# regulator.net
KiCad netlist of a schematic drawn in EAGLE
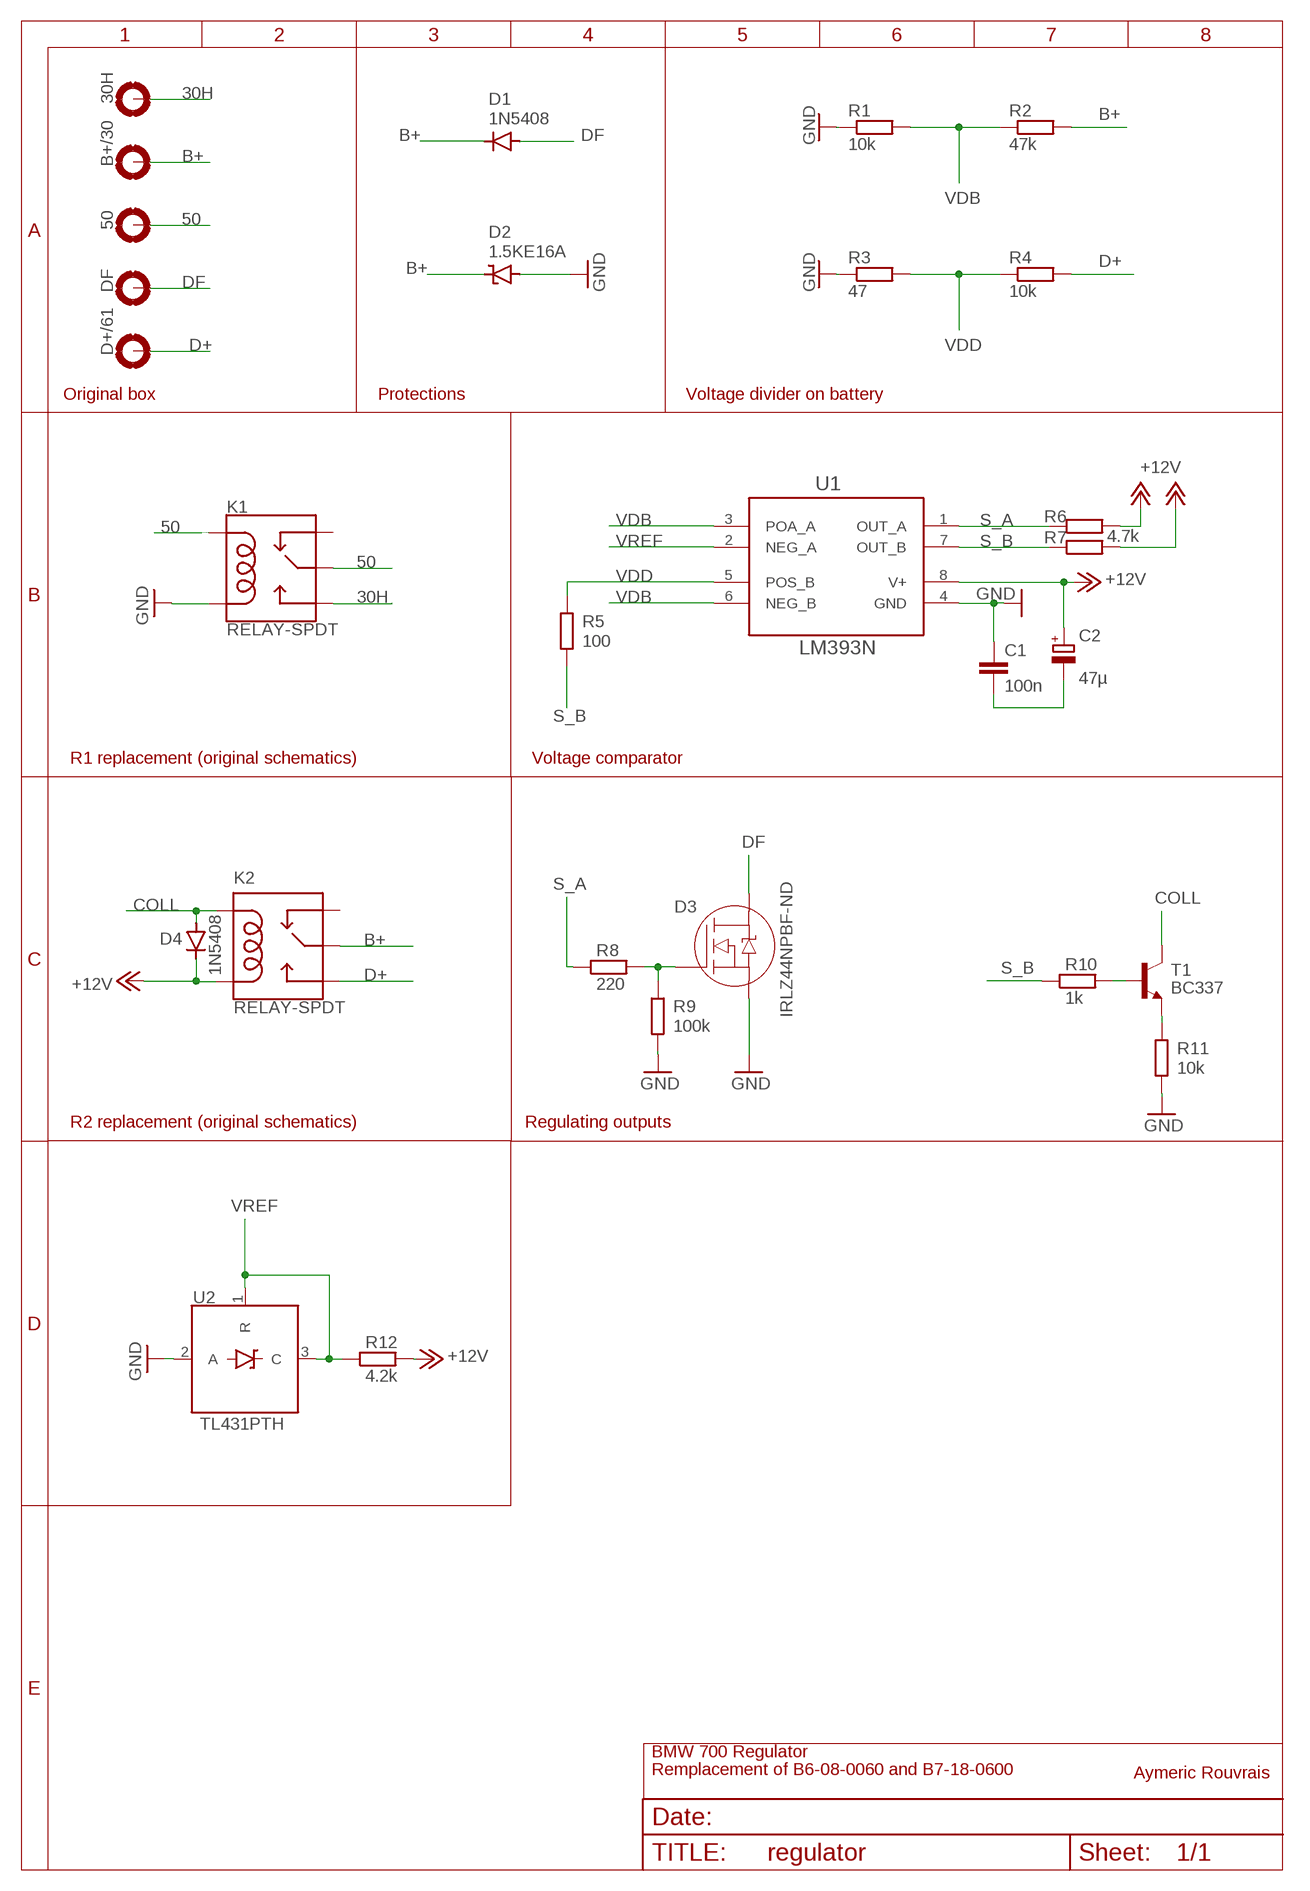
[diagram p0: schematic, sheet 1]

(export (version "E")
  (design (tool "Eeschema 10.0.6"))
  (components
    (comp (ref "30H")
      (value "MOUNT-PAD-ROUND3.0")
      (footprint "eagle-import:3,0-PAD")
      (libsource (lib "eagle-import") (part "MOUNT-PAD-ROUND3.0"))
    )
    (comp (ref "50")
      (value "MOUNT-PAD-ROUND3.0")
      (footprint "eagle-import:3,0-PAD")
      (libsource (lib "eagle-import") (part "MOUNT-PAD-ROUND3.0"))
    )
    (comp (ref "B+/30")
      (value "MOUNT-PAD-ROUND3.0")
      (footprint "eagle-import:3,0-PAD")
      (libsource (lib "eagle-import") (part "MOUNT-PAD-ROUND3.0"))
    )
    (comp (ref "C1")
      (value "100n")
      (footprint "eagle-import:C050-025X075")
      (libsource (lib "eagle-import") (part "C-EU050-025X075"))
    )
    (comp (ref "C2")
      (value "47µ")
      (footprint "eagle-import:E2,5-7")
      (libsource (lib "eagle-import") (part "CPOL-EUE2.5-7"))
    )
    (comp (ref "D+/61")
      (value "MOUNT-PAD-ROUND3.0")
      (footprint "eagle-import:3,0-PAD")
      (libsource (lib "eagle-import") (part "MOUNT-PAD-ROUND3.0"))
    )
    (comp (ref "D1")
      (value "1N5408")
      (footprint "eagle-import:1N5408")
      (fields (field (name "MF") "Littelfuse") (field (name "MP") "1.5KE75A"))
      (libsource (lib "eagle-import") (part "1N5408"))
    )
    (comp (ref "D2")
      (value "1.5KE16A")
      (footprint "eagle-import:1.5KE16A")
      (fields (field (name "MF") "Littelfuse"))
      (libsource (lib "eagle-import") (part "1.5KE16A"))
    )
    (comp (ref "D3")
      (value "IRLZ44NPBF-ND")
      (footprint "eagle-import:TO220AB")
      (fields (field (name "MF") "Taiwan Semiconductor") (field (name "MP") "SR1660"))
      (libsource (lib "eagle-import") (part "IRLZ44NPBF-ND"))
    )
    (comp (ref "D4")
      (value "1N5408")
      (footprint "eagle-import:1N5408")
      (fields (field (name "MF") "Littelfuse") (field (name "MP") "1.5KE75A"))
      (libsource (lib "eagle-import") (part "1N5408"))
    )
    (comp (ref "DF")
      (value "MOUNT-PAD-ROUND3.0")
      (footprint "eagle-import:3,0-PAD")
      (libsource (lib "eagle-import") (part "MOUNT-PAD-ROUND3.0"))
    )
    (comp (ref "K1")
      (value "RELAY-SPDT")
      (footprint "eagle-import:RELAY_G5LE")
      (libsource (lib "eagle-import") (part "RELAY-SPDT"))
    )
    (comp (ref "K2")
      (value "RELAY-SPDT")
      (footprint "eagle-import:RELAY_G5LE")
      (libsource (lib "eagle-import") (part "RELAY-SPDT"))
    )
    (comp (ref "R1")
      (value "10k")
      (footprint "eagle-import:0204_7")
      (libsource (lib "eagle-import") (part "R-EU_0204/7"))
    )
    (comp (ref "R2")
      (value "47k")
      (footprint "eagle-import:0204_7")
      (libsource (lib "eagle-import") (part "R-EU_0204/7"))
    )
    (comp (ref "R3")
      (value "47")
      (footprint "eagle-import:0204_7")
      (libsource (lib "eagle-import") (part "R-EU_0204/7"))
    )
    (comp (ref "R4")
      (value "10k")
      (footprint "eagle-import:0204_7")
      (libsource (lib "eagle-import") (part "R-EU_0204/7"))
    )
    (comp (ref "R5")
      (value "100")
      (footprint "eagle-import:0204_7")
      (libsource (lib "eagle-import") (part "R-EU_0204/7"))
    )
    (comp (ref "R6")
      (value "4.7k")
      (footprint "eagle-import:0204_7")
      (libsource (lib "eagle-import") (part "R-EU_0204/7"))
    )
    (comp (ref "R7")
      (value "4.7k")
      (footprint "eagle-import:0204_7")
      (libsource (lib "eagle-import") (part "R-EU_0204/7"))
    )
    (comp (ref "R8")
      (value "220")
      (footprint "eagle-import:0204_7")
      (libsource (lib "eagle-import") (part "R-EU_0204/7"))
    )
    (comp (ref "R9")
      (value "100k")
      (footprint "eagle-import:0204_7")
      (libsource (lib "eagle-import") (part "R-EU_0204/7"))
    )
    (comp (ref "R10")
      (value "1k")
      (footprint "eagle-import:0204_7")
      (libsource (lib "eagle-import") (part "R-EU_0204/7"))
    )
    (comp (ref "R11")
      (value "10k")
      (footprint "eagle-import:0204_7")
      (libsource (lib "eagle-import") (part "R-EU_0204/7"))
    )
    (comp (ref "R12")
      (value "4.2k")
      (footprint "eagle-import:0204_7")
      (libsource (lib "eagle-import") (part "R-EU_0204/7"))
    )
    (comp (ref "T1")
      (value "BC337")
      (footprint "eagle-import:TO92")
      (libsource (lib "eagle-import") (part "BC337"))
    )
    (comp (ref "U1")
      (value "LM393N")
      (footprint "eagle-import:DIP254P762X508-8")
      (fields (field (name "MF") "STMicroelectronics"))
      (libsource (lib "eagle-import") (part "LM393N"))
    )
    (comp (ref "U2")
      (value "TL431PTH")
      (footprint "eagle-import:TO-92")
      (fields (field (name "MF") "onsemi") (field (name "MP") "TL431"))
      (libsource (lib "eagle-import") (part "TL431PTH"))
    )
  )
  (nets
    (net (code "1") (name "+12V") (class "Default")
      (node (ref "C2") (pin "+") (pinfunction "+_+") (pintype "passive"))
      (node (ref "D4") (pin "1") (pinfunction "C_1") (pintype "passive"))
      (node (ref "K2") (pin "5") (pinfunction "COIL2_5") (pintype "bidirectional"))
      (node (ref "R12") (pin "2") (pinfunction "2_2") (pintype "passive"))
      (node (ref "R6") (pin "2") (pinfunction "2_2") (pintype "passive"))
      (node (ref "R7") (pin "2") (pinfunction "2_2") (pintype "passive"))
      (node (ref "U1") (pin "8") (pinfunction "V+_8") (pintype "power_in"))
    )
    (net (code "2") (name "/30H") (class "Default")
      (node (ref "30H") (pin "B3,0") (pinfunction "MOUNT_B3,0") (pintype "passive"))
      (node (ref "K1") (pin "3") (pinfunction "NO_3") (pintype "bidirectional"))
    )
    (net (code "3") (name "/50") (class "Default")
      (node (ref "50") (pin "B3,0") (pinfunction "MOUNT_B3,0") (pintype "passive"))
      (node (ref "K1") (pin "1") (pinfunction "MAIN_1") (pintype "bidirectional"))
      (node (ref "K1") (pin "2") (pinfunction "COIL1_2") (pintype "bidirectional"))
    )
    (net (code "4") (name "/B+") (class "Default")
      (node (ref "B+/30") (pin "B3,0") (pinfunction "MOUNT_B3,0") (pintype "passive"))
      (node (ref "D1") (pin "1") (pinfunction "C_1") (pintype "passive"))
      (node (ref "D2") (pin "1") (pinfunction "C_1") (pintype "passive"))
      (node (ref "K2") (pin "1") (pinfunction "MAIN_1") (pintype "bidirectional"))
      (node (ref "R2") (pin "2") (pinfunction "2_2") (pintype "passive"))
    )
    (net (code "5") (name "/COLL") (class "Default")
      (node (ref "D4") (pin "2") (pinfunction "A_2") (pintype "passive"))
      (node (ref "K2") (pin "2") (pinfunction "COIL1_2") (pintype "bidirectional"))
      (node (ref "T1") (pin "3") (pinfunction "C_3") (pintype "passive"))
    )
    (net (code "6") (name "/D+") (class "Default")
      (node (ref "D+/61") (pin "B3,0") (pinfunction "MOUNT_B3,0") (pintype "passive"))
      (node (ref "K2") (pin "3") (pinfunction "NO_3") (pintype "bidirectional"))
      (node (ref "R4") (pin "2") (pinfunction "2_2") (pintype "passive"))
    )
    (net (code "7") (name "/DF") (class "Default")
      (node (ref "D1") (pin "2") (pinfunction "A_2") (pintype "passive"))
      (node (ref "D3") (pin "1") (pinfunction "D_1") (pintype "passive"))
      (node (ref "DF") (pin "B3,0") (pinfunction "MOUNT_B3,0") (pintype "passive"))
    )
    (net (code "8") (name "/S_A") (class "Default")
      (node (ref "R6") (pin "1") (pinfunction "1_1") (pintype "passive"))
      (node (ref "R8") (pin "1") (pinfunction "1_1") (pintype "passive"))
      (node (ref "U1") (pin "1") (pinfunction "OUT_A_1") (pintype "output"))
    )
    (net (code "9") (name "/S_B") (class "Default")
      (node (ref "R10") (pin "1") (pinfunction "1_1") (pintype "passive"))
      (node (ref "R5") (pin "1") (pinfunction "1_1") (pintype "passive"))
      (node (ref "R7") (pin "1") (pinfunction "1_1") (pintype "passive"))
      (node (ref "U1") (pin "7") (pinfunction "OUT_B_7") (pintype "output"))
    )
    (net (code "10") (name "/VDB") (class "Default")
      (node (ref "R1") (pin "2") (pinfunction "2_2") (pintype "passive"))
      (node (ref "R2") (pin "1") (pinfunction "1_1") (pintype "passive"))
      (node (ref "U1") (pin "3") (pinfunction "POA_A_3") (pintype "input"))
      (node (ref "U1") (pin "6") (pinfunction "NEG_B_6") (pintype "input"))
    )
    (net (code "11") (name "/VDD") (class "Default")
      (node (ref "R3") (pin "2") (pinfunction "2_2") (pintype "passive"))
      (node (ref "R4") (pin "1") (pinfunction "1_1") (pintype "passive"))
      (node (ref "R5") (pin "2") (pinfunction "2_2") (pintype "passive"))
      (node (ref "U1") (pin "5") (pinfunction "POS_B_5") (pintype "input"))
    )
    (net (code "12") (name "/VREF") (class "Default")
      (node (ref "R12") (pin "1") (pinfunction "1_1") (pintype "passive"))
      (node (ref "U1") (pin "2") (pinfunction "NEG_A_2") (pintype "input"))
      (node (ref "U2") (pin "1") (pinfunction "R_1") (pintype "bidirectional"))
      (node (ref "U2") (pin "3") (pinfunction "C_3") (pintype "bidirectional"))
    )
    (net (code "13") (name "GND") (class "Default")
      (node (ref "C1") (pin "1") (pinfunction "1_1") (pintype "passive"))
      (node (ref "D2") (pin "2") (pinfunction "A_2") (pintype "passive"))
      (node (ref "D3") (pin "3") (pinfunction "S_3") (pintype "passive"))
      (node (ref "K1") (pin "5") (pinfunction "COIL2_5") (pintype "bidirectional"))
      (node (ref "R1") (pin "1") (pinfunction "1_1") (pintype "passive"))
      (node (ref "R11") (pin "1") (pinfunction "1_1") (pintype "passive"))
      (node (ref "R3") (pin "1") (pinfunction "1_1") (pintype "passive"))
      (node (ref "R9") (pin "2") (pinfunction "2_2") (pintype "passive"))
      (node (ref "U1") (pin "4") (pinfunction "GND_4") (pintype "passive"))
      (node (ref "U2") (pin "2") (pinfunction "A_2") (pintype "bidirectional"))
    )
    (net (code "14") (name "Net-(C1-Pad2)") (class "Default")
      (node (ref "C1") (pin "2") (pinfunction "2_2") (pintype "passive"))
      (node (ref "C2") (pin "-") (pinfunction "-_-") (pintype "passive"))
    )
    (net (code "15") (name "Net-(D3-G)") (class "Default")
      (node (ref "D3") (pin "2") (pinfunction "G_2") (pintype "passive"))
      (node (ref "R8") (pin "2") (pinfunction "2_2") (pintype "passive"))
      (node (ref "R9") (pin "1") (pinfunction "1_1") (pintype "passive"))
    )
    (net (code "16") (name "Net-(T1-B)") (class "Default")
      (node (ref "R10") (pin "2") (pinfunction "2_2") (pintype "passive"))
      (node (ref "T1") (pin "2") (pinfunction "B_2") (pintype "passive"))
    )
    (net (code "17") (name "Net-(T1-E)") (class "Default")
      (node (ref "R11") (pin "2") (pinfunction "2_2") (pintype "passive"))
      (node (ref "T1") (pin "1") (pinfunction "E_1") (pintype "passive"))
    )
    (net (code "18") (name "unconnected-(K1-NC-Pad4)") (class "Default")
      (node (ref "K1") (pin "4") (pinfunction "NC_4") (pintype "bidirectional"))
    )
    (net (code "19") (name "unconnected-(K2-NC-Pad4)") (class "Default")
      (node (ref "K2") (pin "4") (pinfunction "NC_4") (pintype "bidirectional"))
    )
  )
)
